# BLE_module.net
KiCad netlist of a schematic drawn in Altium Designer
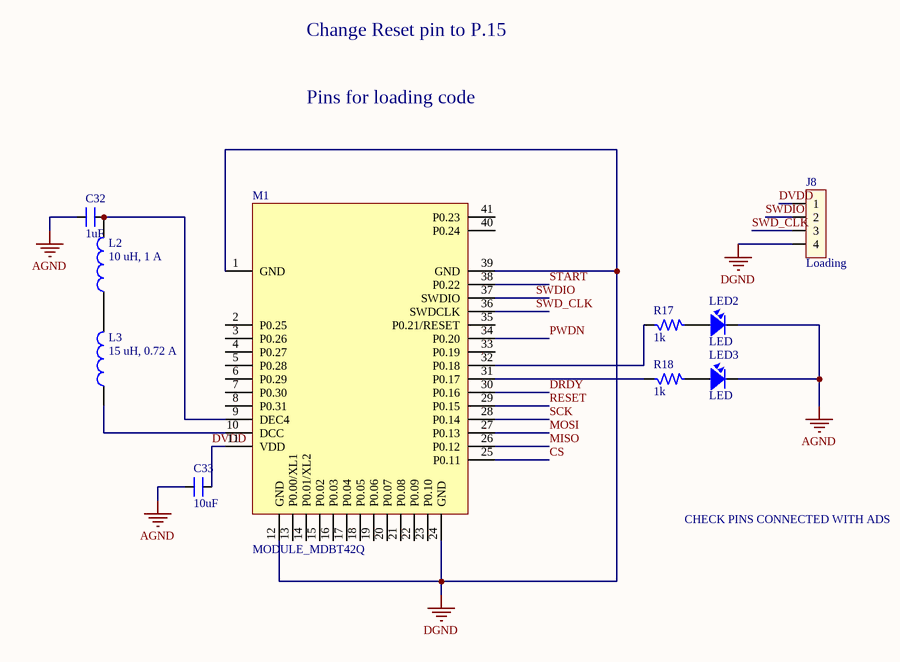
[diagram p0: BLE module.SchDoc]

(export (version "E")
  (design (tool "Eeschema 10.0.6"))
  (components
    (comp (ref "C32")
      (value "1uF")
      (footprint "SM-0805")
      (description "Cap SMD")
      (libsource (lib "VioletofSun") (part "CM"))
    )
    (comp (ref "C33")
      (value "10uF")
      (footprint "SM-0805")
      (description "Cap SMD")
      (libsource (lib "VioletofSun") (part "CM"))
    )
    (comp (ref "J8")
      (value "Loading")
      (footprint "JP4")
      (description "Connector 4")
      (libsource (lib "VioletofSun") (part "JP4"))
    )
    (comp (ref "L2")
      (value "10 uH, 1 A")
      (footprint "WE-TPC_2828")
      (description "SMT Shielded Tiny Power Inductor WE-TPC, size 2828, 10 uH, 1 A")
      (fields (field (name "PART NUMBER") "744025100") (field (name "PUBLISHER") "Wurth Elektronik"))
      (libsource (lib "ALTIUM-WE-TPC-rev18a") (part "744025100"))
    )
    (comp (ref "L3")
      (value "15 uH, 0.72 A")
      (footprint "WE-TPC_2828")
      (description "SMT Shielded Tiny Power Inductor WE-TPC, size 2828, 15 uH, 0.72 A")
      (fields (field (name "PART NUMBER") "744025150") (field (name "PUBLISHER") "Wurth Elektronik"))
      (libsource (lib "ALTIUM-WE-TPC-rev18a") (part "744025150"))
    )
    (comp (ref "LED2")
      (value "LED")
      (footprint "SM-0805")
      (description "LED Single colour Green and Red")
      (libsource (lib "VioletofSun") (part "LED"))
    )
    (comp (ref "LED3")
      (value "LED")
      (footprint "SM-0805")
      (description "LED Single colour Green and Red")
      (libsource (lib "VioletofSun") (part "LED"))
    )
    (comp (ref "M1")
      (value "MODULE_MDBT42Q")
      (footprint "PCB_MDBT42Q_10X16")
      (description "MDBT42Q")
      (libsource (lib "MDBT42Q_SCHLIB_181015") (part "MODULE_MDBT42Q"))
    )
    (comp (ref "R17")
      (value "1k")
      (footprint "SM-0805")
      (description "Resistor 1/4W")
      (libsource (lib "VioletofSun") (part "R"))
    )
    (comp (ref "R18")
      (value "1k")
      (footprint "SM-0805")
      (description "Resistor 1/4W")
      (libsource (lib "VioletofSun") (part "R"))
    )
  )
  (nets
    (net (code "1") (name "/CS") (class "Default")
      (node (ref "M1") (pin "25") (pinfunction "P0.11_25") (pintype "passive"))
    )
    (net (code "2") (name "/DRDY") (class "Default")
      (node (ref "M1") (pin "30") (pinfunction "P0.16_30") (pintype "passive"))
    )
    (net (code "3") (name "/DVDD") (class "Default")
      (node (ref "C33") (pin "2") (pinfunction "2_2") (pintype "passive"))
      (node (ref "J8") (pin "1") (pinfunction "1_1") (pintype "passive"))
      (node (ref "M1") (pin "11") (pinfunction "VDD_11") (pintype "passive"))
    )
    (net (code "4") (name "/MISO") (class "Default")
      (node (ref "M1") (pin "26") (pinfunction "P0.12_26") (pintype "passive"))
    )
    (net (code "5") (name "/MOSI") (class "Default")
      (node (ref "M1") (pin "27") (pinfunction "P0.13_27") (pintype "passive"))
    )
    (net (code "6") (name "/PWDN") (class "Default")
      (node (ref "M1") (pin "34") (pinfunction "P0.20_34") (pintype "passive"))
    )
    (net (code "7") (name "/RESET") (class "Default")
      (node (ref "M1") (pin "29") (pinfunction "P0.15_29") (pintype "passive"))
    )
    (net (code "8") (name "/SCK") (class "Default")
      (node (ref "M1") (pin "28") (pinfunction "P0.14_28") (pintype "passive"))
    )
    (net (code "9") (name "/START") (class "Default")
      (node (ref "M1") (pin "38") (pinfunction "P0.22_38") (pintype "passive"))
    )
    (net (code "10") (name "/SWDIO") (class "Default")
      (node (ref "J8") (pin "2") (pinfunction "2_2") (pintype "passive"))
      (node (ref "M1") (pin "37") (pinfunction "SWDIO_37") (pintype "passive"))
    )
    (net (code "11") (name "/SWD_CLK") (class "Default")
      (node (ref "J8") (pin "3") (pinfunction "3_3") (pintype "passive"))
      (node (ref "M1") (pin "36") (pinfunction "SWDCLK_36") (pintype "passive"))
    )
    (net (code "12") (name "AGND") (class "Default")
      (node (ref "C32") (pin "1") (pinfunction "1_1") (pintype "passive"))
      (node (ref "C33") (pin "1") (pinfunction "1_1") (pintype "passive"))
      (node (ref "LED2") (pin "2") (pinfunction "2_2") (pintype "passive"))
      (node (ref "LED3") (pin "2") (pinfunction "2_2") (pintype "passive"))
    )
    (net (code "13") (name "DGND") (class "Default")
      (node (ref "J8") (pin "4") (pinfunction "4_4") (pintype "passive"))
      (node (ref "M1") (pin "1") (pinfunction "GND_1") (pintype "passive"))
      (node (ref "M1") (pin "12") (pinfunction "GND_12") (pintype "passive"))
      (node (ref "M1") (pin "24") (pinfunction "GND_24") (pintype "passive"))
      (node (ref "M1") (pin "39") (pinfunction "GND_39") (pintype "passive"))
    )
    (net (code "14") (name "Net-(L2-Pad1)") (class "Default")
      (node (ref "L2") (pin "1") (pinfunction "1_1") (pintype "passive"))
      (node (ref "L3") (pin "2") (pinfunction "2_2") (pintype "passive"))
    )
    (net (code "15") (name "Net-(LED2-Pad1)") (class "Default")
      (node (ref "LED2") (pin "1") (pinfunction "1_1") (pintype "passive"))
      (node (ref "R17") (pin "2") (pinfunction "2_2") (pintype "passive"))
    )
    (net (code "16") (name "Net-(LED3-Pad1)") (class "Default")
      (node (ref "LED3") (pin "1") (pinfunction "1_1") (pintype "passive"))
      (node (ref "R18") (pin "2") (pinfunction "2_2") (pintype "passive"))
    )
    (net (code "17") (name "Net-(M1-DCC)") (class "Default")
      (node (ref "L3") (pin "1") (pinfunction "1_1") (pintype "passive"))
      (node (ref "M1") (pin "10") (pinfunction "DCC_10") (pintype "passive"))
    )
    (net (code "18") (name "Net-(M1-DEC4)") (class "Default")
      (node (ref "C32") (pin "2") (pinfunction "2_2") (pintype "passive"))
      (node (ref "L2") (pin "2") (pinfunction "2_2") (pintype "passive"))
      (node (ref "M1") (pin "9") (pinfunction "DEC4_9") (pintype "passive"))
    )
    (net (code "19") (name "Net-(M1-P0.17)") (class "Default")
      (node (ref "M1") (pin "31") (pinfunction "P0.17_31") (pintype "passive"))
      (node (ref "R18") (pin "1") (pinfunction "1_1") (pintype "passive"))
    )
    (net (code "20") (name "Net-(M1-P0.18)") (class "Default")
      (node (ref "M1") (pin "32") (pinfunction "P0.18_32") (pintype "passive"))
      (node (ref "R17") (pin "1") (pinfunction "1_1") (pintype "passive"))
    )
    (net (code "21") (name "unconnected-(M1-P0.00{slash}XL1-Pad13)") (class "Default")
      (node (ref "M1") (pin "13") (pinfunction "P0.00/XL1_13") (pintype "passive"))
    )
    (net (code "22") (name "unconnected-(M1-P0.01{slash}XL2-Pad14)") (class "Default")
      (node (ref "M1") (pin "14") (pinfunction "P0.01/XL2_14") (pintype "passive"))
    )
    (net (code "23") (name "unconnected-(M1-P0.02-Pad15)") (class "Default")
      (node (ref "M1") (pin "15") (pinfunction "P0.02_15") (pintype "passive"))
    )
    (net (code "24") (name "unconnected-(M1-P0.03-Pad16)") (class "Default")
      (node (ref "M1") (pin "16") (pinfunction "P0.03_16") (pintype "passive"))
    )
    (net (code "25") (name "unconnected-(M1-P0.04-Pad17)") (class "Default")
      (node (ref "M1") (pin "17") (pinfunction "P0.04_17") (pintype "passive"))
    )
    (net (code "26") (name "unconnected-(M1-P0.05-Pad18)") (class "Default")
      (node (ref "M1") (pin "18") (pinfunction "P0.05_18") (pintype "passive"))
    )
    (net (code "27") (name "unconnected-(M1-P0.06-Pad19)") (class "Default")
      (node (ref "M1") (pin "19") (pinfunction "P0.06_19") (pintype "passive"))
    )
    (net (code "28") (name "unconnected-(M1-P0.07-Pad20)") (class "Default")
      (node (ref "M1") (pin "20") (pinfunction "P0.07_20") (pintype "passive"))
    )
    (net (code "29") (name "unconnected-(M1-P0.08-Pad21)") (class "Default")
      (node (ref "M1") (pin "21") (pinfunction "P0.08_21") (pintype "passive"))
    )
    (net (code "30") (name "unconnected-(M1-P0.09-Pad22)") (class "Default")
      (node (ref "M1") (pin "22") (pinfunction "P0.09_22") (pintype "passive"))
    )
    (net (code "31") (name "unconnected-(M1-P0.10-Pad23)") (class "Default")
      (node (ref "M1") (pin "23") (pinfunction "P0.10_23") (pintype "passive"))
    )
    (net (code "32") (name "unconnected-(M1-P0.19-Pad33)") (class "Default")
      (node (ref "M1") (pin "33") (pinfunction "P0.19_33") (pintype "passive"))
    )
    (net (code "33") (name "unconnected-(M1-P0.21{slash}RESET-Pad35)") (class "Default")
      (node (ref "M1") (pin "35") (pinfunction "P0.21/RESET_35") (pintype "passive"))
    )
    (net (code "34") (name "unconnected-(M1-P0.23-Pad41)") (class "Default")
      (node (ref "M1") (pin "41") (pinfunction "P0.23_41") (pintype "passive"))
    )
    (net (code "35") (name "unconnected-(M1-P0.24-Pad40)") (class "Default")
      (node (ref "M1") (pin "40") (pinfunction "P0.24_40") (pintype "passive"))
    )
    (net (code "36") (name "unconnected-(M1-P0.25-Pad2)") (class "Default")
      (node (ref "M1") (pin "2") (pinfunction "P0.25_2") (pintype "passive"))
    )
    (net (code "37") (name "unconnected-(M1-P0.26-Pad3)") (class "Default")
      (node (ref "M1") (pin "3") (pinfunction "P0.26_3") (pintype "passive"))
    )
    (net (code "38") (name "unconnected-(M1-P0.27-Pad4)") (class "Default")
      (node (ref "M1") (pin "4") (pinfunction "P0.27_4") (pintype "passive"))
    )
    (net (code "39") (name "unconnected-(M1-P0.28-Pad5)") (class "Default")
      (node (ref "M1") (pin "5") (pinfunction "P0.28_5") (pintype "passive"))
    )
    (net (code "40") (name "unconnected-(M1-P0.29-Pad6)") (class "Default")
      (node (ref "M1") (pin "6") (pinfunction "P0.29_6") (pintype "passive"))
    )
    (net (code "41") (name "unconnected-(M1-P0.30-Pad7)") (class "Default")
      (node (ref "M1") (pin "7") (pinfunction "P0.30_7") (pintype "passive"))
    )
    (net (code "42") (name "unconnected-(M1-P0.31-Pad8)") (class "Default")
      (node (ref "M1") (pin "8") (pinfunction "P0.31_8") (pintype "passive"))
    )
  )
)
